# RPi-Camera-RingLicht_v10.net
KiCad netlist of a schematic drawn in EAGLE
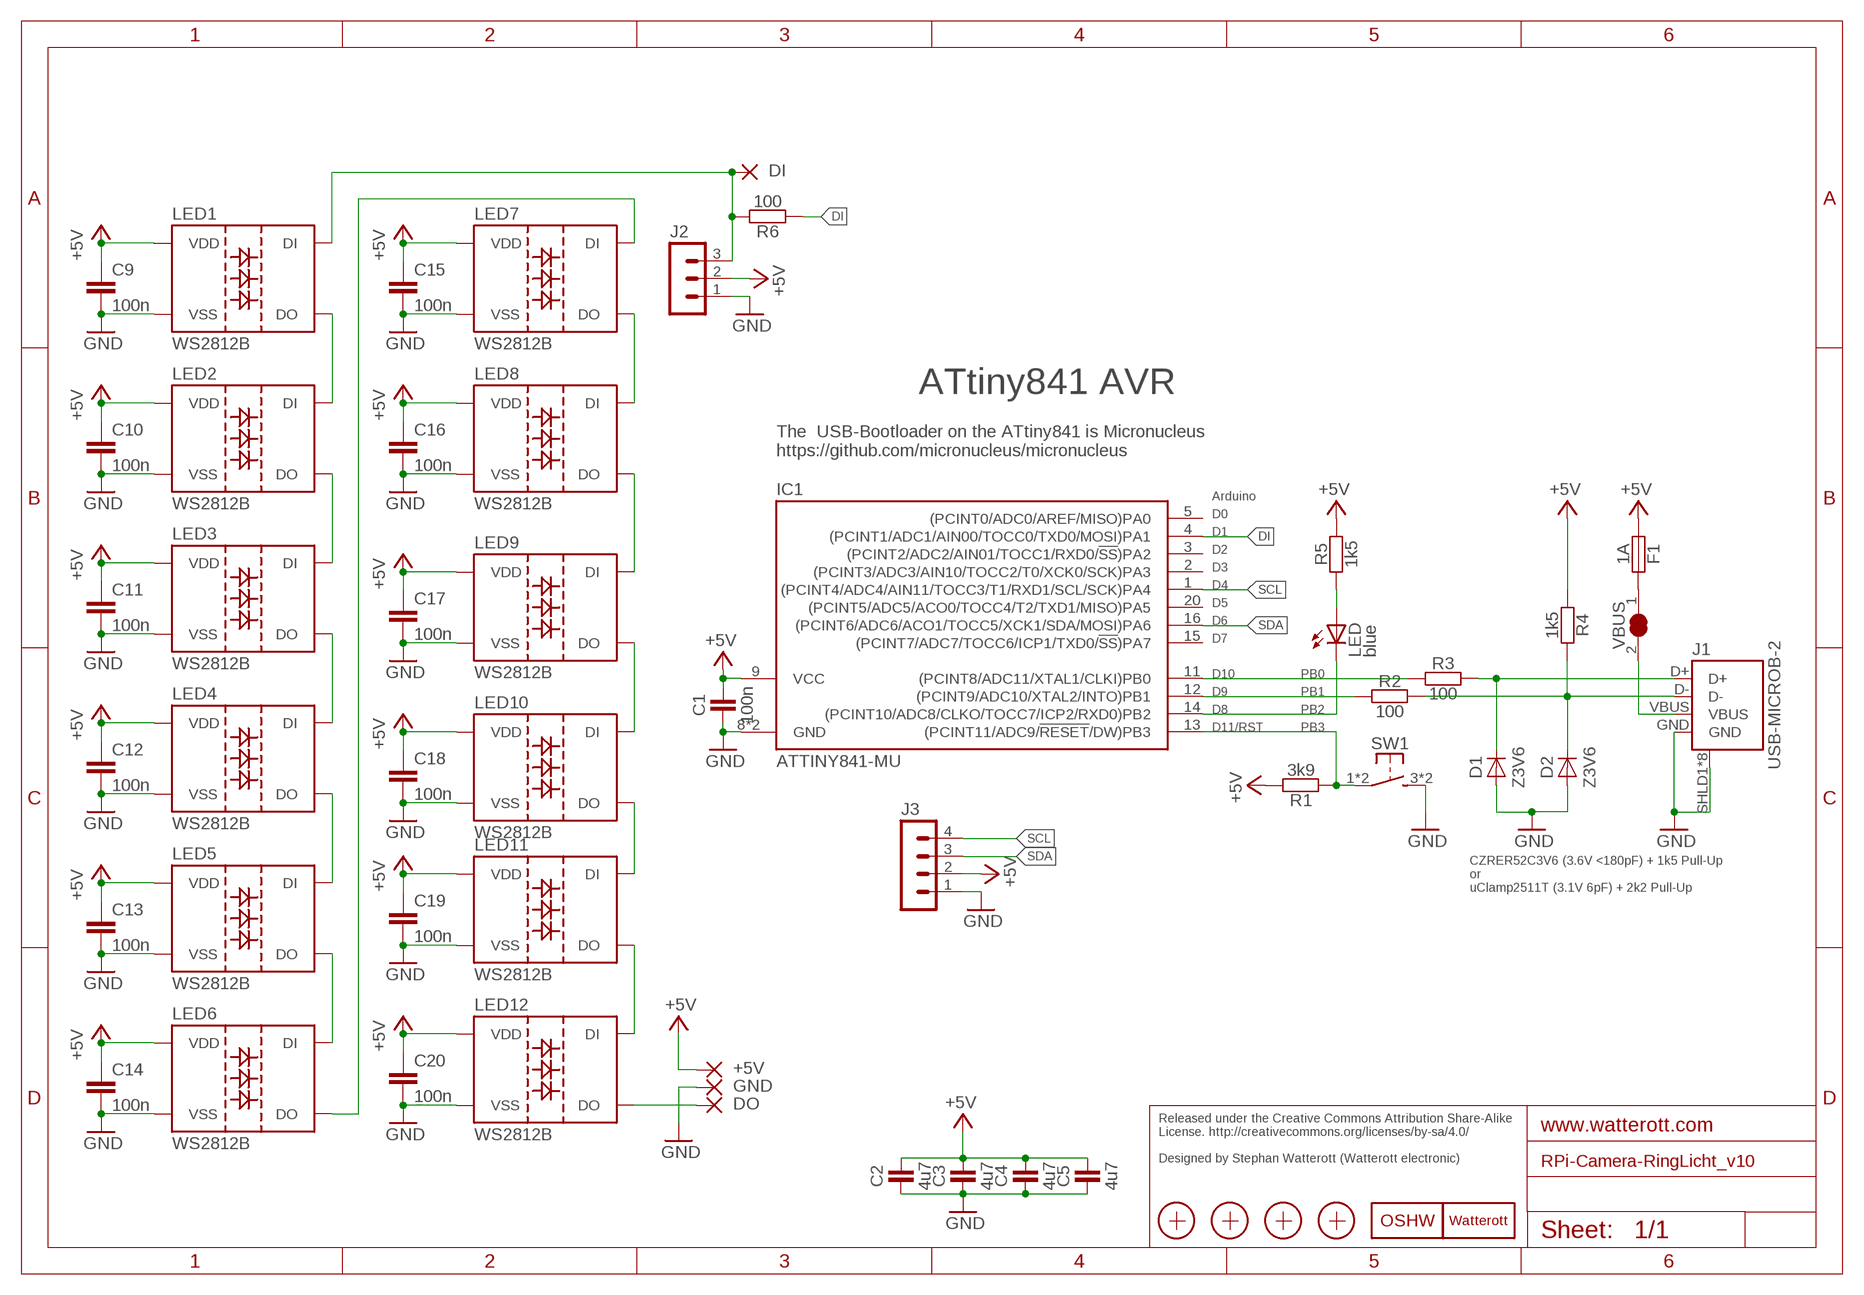
[diagram p0: schematic, sheet 1]

(export (version "E")
  (design (tool "Eeschema 10.0.6"))
  (components
    (comp (ref "+5V")
      (value "SMD2")
      (footprint "eagle-import:SMD1,27-2,54")
      (libsource (lib "eagle-import") (part "SMD2"))
    )
    (comp (ref "C1")
      (value "100n")
      (footprint "eagle-import:C0402")
      (libsource (lib "eagle-import") (part "CAPACITOR-0402"))
    )
    (comp (ref "C2")
      (value "4u7")
      (footprint "eagle-import:C0402")
      (libsource (lib "eagle-import") (part "CAPACITOR-0402"))
    )
    (comp (ref "C3")
      (value "4u7")
      (footprint "eagle-import:C0402")
      (libsource (lib "eagle-import") (part "CAPACITOR-0402"))
    )
    (comp (ref "C4")
      (value "4u7")
      (footprint "eagle-import:C0402")
      (libsource (lib "eagle-import") (part "CAPACITOR-0402"))
    )
    (comp (ref "C5")
      (value "4u7")
      (footprint "eagle-import:C0402")
      (libsource (lib "eagle-import") (part "CAPACITOR-0402"))
    )
    (comp (ref "C9")
      (value "100n")
      (footprint "eagle-import:C0402K")
      (libsource (lib "eagle-import") (part "C-EUC0402K"))
    )
    (comp (ref "C10")
      (value "100n")
      (footprint "eagle-import:C0402K")
      (libsource (lib "eagle-import") (part "C-EUC0402K"))
    )
    (comp (ref "C11")
      (value "100n")
      (footprint "eagle-import:C0402K")
      (libsource (lib "eagle-import") (part "C-EUC0402K"))
    )
    (comp (ref "C12")
      (value "100n")
      (footprint "eagle-import:C0402K")
      (libsource (lib "eagle-import") (part "C-EUC0402K"))
    )
    (comp (ref "C13")
      (value "100n")
      (footprint "eagle-import:C0402K")
      (libsource (lib "eagle-import") (part "C-EUC0402K"))
    )
    (comp (ref "C14")
      (value "100n")
      (footprint "eagle-import:C0402K")
      (libsource (lib "eagle-import") (part "C-EUC0402K"))
    )
    (comp (ref "C15")
      (value "100n")
      (footprint "eagle-import:C0402K")
      (libsource (lib "eagle-import") (part "C-EUC0402K"))
    )
    (comp (ref "C16")
      (value "100n")
      (footprint "eagle-import:C0402K")
      (libsource (lib "eagle-import") (part "C-EUC0402K"))
    )
    (comp (ref "C17")
      (value "100n")
      (footprint "eagle-import:C0402K")
      (libsource (lib "eagle-import") (part "C-EUC0402K"))
    )
    (comp (ref "C18")
      (value "100n")
      (footprint "eagle-import:C0402K")
      (libsource (lib "eagle-import") (part "C-EUC0402K"))
    )
    (comp (ref "C19")
      (value "100n")
      (footprint "eagle-import:C0402K")
      (libsource (lib "eagle-import") (part "C-EUC0402K"))
    )
    (comp (ref "C20")
      (value "100n")
      (footprint "eagle-import:C0402K")
      (libsource (lib "eagle-import") (part "C-EUC0402K"))
    )
    (comp (ref "D1")
      (value "Z3V6")
      (footprint "eagle-import:SOD882")
      (libsource (lib "eagle-import") (part "DIODE-SOD882"))
    )
    (comp (ref "D2")
      (value "Z3V6")
      (footprint "eagle-import:SOD882")
      (libsource (lib "eagle-import") (part "DIODE-SOD882"))
    )
    (comp (ref "DI")
      (value "SMD2")
      (footprint "eagle-import:SMD1,27-2,54")
      (libsource (lib "eagle-import") (part "SMD2"))
    )
    (comp (ref "DO")
      (value "SMD2")
      (footprint "eagle-import:SMD1,27-2,54")
      (libsource (lib "eagle-import") (part "SMD2"))
    )
    (comp (ref "F1")
      (value "1A")
      (footprint "eagle-import:C0805")
      (libsource (lib "eagle-import") (part "FUSE-0805"))
    )
    (comp (ref "GND")
      (value "SMD2")
      (footprint "eagle-import:SMD1,27-2,54")
      (libsource (lib "eagle-import") (part "SMD2"))
    )
    (comp (ref "IC1")
      (value "ATTINY841-MU")
      (footprint "eagle-import:QFN20-PAD")
      (libsource (lib "eagle-import") (part "ATTINY841-MU"))
    )
    (comp (ref "J1")
      (value "USB-MICROB-2")
      (footprint "eagle-import:USB-MICROB-10118194")
      (libsource (lib "eagle-import") (part "USB-MICROB-2"))
    )
    (comp (ref "J2")
      (value "JST3-S3B-PH-SM4-TB")
      (footprint "eagle-import:JST_S3B-PH-SM4-TB")
      (libsource (lib "eagle-import") (part "JST3-S3B-PH-SM4-TB"))
    )
    (comp (ref "J3")
      (value "JST4-S4B-PH-SM4-TB")
      (footprint "eagle-import:JST_S4B-PH-SM4-TB")
      (libsource (lib "eagle-import") (part "JST4-S4B-PH-SM4-TB"))
    )
    (comp (ref "LED")
      (value "blue")
      (footprint "eagle-import:C0603")
      (libsource (lib "eagle-import") (part "LED-0603"))
    )
    (comp (ref "LED1")
      (value "WS2812B")
      (footprint "eagle-import:WS2812B")
      (libsource (lib "eagle-import") (part "WS2812B"))
    )
    (comp (ref "LED2")
      (value "WS2812B")
      (footprint "eagle-import:WS2812B")
      (libsource (lib "eagle-import") (part "WS2812B"))
    )
    (comp (ref "LED3")
      (value "WS2812B")
      (footprint "eagle-import:WS2812B")
      (libsource (lib "eagle-import") (part "WS2812B"))
    )
    (comp (ref "LED4")
      (value "WS2812B")
      (footprint "eagle-import:WS2812B")
      (libsource (lib "eagle-import") (part "WS2812B"))
    )
    (comp (ref "LED5")
      (value "WS2812B")
      (footprint "eagle-import:WS2812B")
      (libsource (lib "eagle-import") (part "WS2812B"))
    )
    (comp (ref "LED6")
      (value "WS2812B")
      (footprint "eagle-import:WS2812B")
      (libsource (lib "eagle-import") (part "WS2812B"))
    )
    (comp (ref "LED7")
      (value "WS2812B")
      (footprint "eagle-import:WS2812B")
      (libsource (lib "eagle-import") (part "WS2812B"))
    )
    (comp (ref "LED8")
      (value "WS2812B")
      (footprint "eagle-import:WS2812B")
      (libsource (lib "eagle-import") (part "WS2812B"))
    )
    (comp (ref "LED9")
      (value "WS2812B")
      (footprint "eagle-import:WS2812B")
      (libsource (lib "eagle-import") (part "WS2812B"))
    )
    (comp (ref "LED10")
      (value "WS2812B")
      (footprint "eagle-import:WS2812B")
      (libsource (lib "eagle-import") (part "WS2812B"))
    )
    (comp (ref "LED11")
      (value "WS2812B")
      (footprint "eagle-import:WS2812B")
      (libsource (lib "eagle-import") (part "WS2812B"))
    )
    (comp (ref "LED12")
      (value "WS2812B")
      (footprint "eagle-import:WS2812B")
      (libsource (lib "eagle-import") (part "WS2812B"))
    )
    (comp (ref "LOGO1")
      (value "LOGO-S_PLACE_M")
      (footprint "eagle-import:SPARK_TPLACE_M")
      (libsource (lib "eagle-import") (part "LOGO-S_PLACE_M"))
    )
    (comp (ref "LOGO2")
      (value "OSHW_LOGOX0070")
      (footprint "eagle-import:OSHW_6X70")
      (libsource (lib "eagle-import") (part "OSHW_LOGOX0070"))
    )
    (comp (ref "R1")
      (value "3k9")
      (footprint "eagle-import:C0402")
      (libsource (lib "eagle-import") (part "RESISTOR-0402"))
    )
    (comp (ref "R2")
      (value "100")
      (footprint "eagle-import:C0402")
      (libsource (lib "eagle-import") (part "RESISTOR-0402"))
    )
    (comp (ref "R3")
      (value "100")
      (footprint "eagle-import:C0402")
      (libsource (lib "eagle-import") (part "RESISTOR-0402"))
    )
    (comp (ref "R4")
      (value "1k5")
      (footprint "eagle-import:C0402")
      (libsource (lib "eagle-import") (part "RESISTOR-0402"))
    )
    (comp (ref "R5")
      (value "1k5")
      (footprint "eagle-import:C0402")
      (libsource (lib "eagle-import") (part "RESISTOR-0402"))
    )
    (comp (ref "R6")
      (value "100")
      (footprint "eagle-import:C0402")
      (libsource (lib "eagle-import") (part "RESISTOR-0402"))
    )
    (comp (ref "SW1")
      (value "SW-TACTILE-PTS840P")
      (footprint "eagle-import:PTS840P")
      (libsource (lib "eagle-import") (part "SW-TACTILE-PTS840P"))
    )
    (comp (ref "VBUS")
      (value "JUMPER2-0603-NC")
      (footprint "eagle-import:JUMPER2-0603_NC")
      (libsource (lib "eagle-import") (part "JUMPER2-0603-NC"))
    )
    (comp (ref "X1")
      (value "PASSER-07")
      (footprint "eagle-import:PASSER_07MM")
      (libsource (lib "eagle-import") (part "PASSER-07"))
    )
    (comp (ref "X2")
      (value "PASSER-07")
      (footprint "eagle-import:PASSER_07MM")
      (libsource (lib "eagle-import") (part "PASSER-07"))
    )
    (comp (ref "X3")
      (value "PASSER-07")
      (footprint "eagle-import:PASSER_07MM")
      (libsource (lib "eagle-import") (part "PASSER-07"))
    )
    (comp (ref "X4")
      (value "PASSER-07")
      (footprint "eagle-import:PASSER_07MM")
      (libsource (lib "eagle-import") (part "PASSER-07"))
    )
  )
  (nets
    (net (code "1") (name "+5V") (class "Default")
      (node (ref "+5V") (pin "1") (pinfunction "P_1") (pintype "passive"))
      (node (ref "C1") (pin "2") (pinfunction "2_2") (pintype "passive"))
      (node (ref "C10") (pin "1") (pinfunction "1_1") (pintype "passive"))
      (node (ref "C11") (pin "1") (pinfunction "1_1") (pintype "passive"))
      (node (ref "C12") (pin "1") (pinfunction "1_1") (pintype "passive"))
      (node (ref "C13") (pin "1") (pinfunction "1_1") (pintype "passive"))
      (node (ref "C14") (pin "1") (pinfunction "1_1") (pintype "passive"))
      (node (ref "C15") (pin "1") (pinfunction "1_1") (pintype "passive"))
      (node (ref "C16") (pin "1") (pinfunction "1_1") (pintype "passive"))
      (node (ref "C17") (pin "1") (pinfunction "1_1") (pintype "passive"))
      (node (ref "C18") (pin "1") (pinfunction "1_1") (pintype "passive"))
      (node (ref "C19") (pin "1") (pinfunction "1_1") (pintype "passive"))
      (node (ref "C2") (pin "2") (pinfunction "2_2") (pintype "passive"))
      (node (ref "C20") (pin "1") (pinfunction "1_1") (pintype "passive"))
      (node (ref "C3") (pin "2") (pinfunction "2_2") (pintype "passive"))
      (node (ref "C4") (pin "2") (pinfunction "2_2") (pintype "passive"))
      (node (ref "C5") (pin "2") (pinfunction "2_2") (pintype "passive"))
      (node (ref "C9") (pin "1") (pinfunction "1_1") (pintype "passive"))
      (node (ref "F1") (pin "1") (pinfunction "1_1") (pintype "passive"))
      (node (ref "IC1") (pin "9") (pinfunction "VCC_9") (pintype "power_in"))
      (node (ref "J2") (pin "2") (pinfunction "2_2") (pintype "passive"))
      (node (ref "J3") (pin "2") (pinfunction "2_2") (pintype "passive"))
      (node (ref "LED1") (pin "1") (pinfunction "VDD_1") (pintype "bidirectional"))
      (node (ref "LED10") (pin "1") (pinfunction "VDD_1") (pintype "bidirectional"))
      (node (ref "LED11") (pin "1") (pinfunction "VDD_1") (pintype "bidirectional"))
      (node (ref "LED12") (pin "1") (pinfunction "VDD_1") (pintype "bidirectional"))
      (node (ref "LED2") (pin "1") (pinfunction "VDD_1") (pintype "bidirectional"))
      (node (ref "LED3") (pin "1") (pinfunction "VDD_1") (pintype "bidirectional"))
      (node (ref "LED4") (pin "1") (pinfunction "VDD_1") (pintype "bidirectional"))
      (node (ref "LED5") (pin "1") (pinfunction "VDD_1") (pintype "bidirectional"))
      (node (ref "LED6") (pin "1") (pinfunction "VDD_1") (pintype "bidirectional"))
      (node (ref "LED7") (pin "1") (pinfunction "VDD_1") (pintype "bidirectional"))
      (node (ref "LED8") (pin "1") (pinfunction "VDD_1") (pintype "bidirectional"))
      (node (ref "LED9") (pin "1") (pinfunction "VDD_1") (pintype "bidirectional"))
      (node (ref "R1") (pin "2") (pinfunction "2_2") (pintype "passive"))
      (node (ref "R4") (pin "1") (pinfunction "1_1") (pintype "passive"))
      (node (ref "R5") (pin "2") (pinfunction "2_2") (pintype "passive"))
    )
    (net (code "2") (name "/PB0") (class "Default")
      (node (ref "IC1") (pin "11") (pinfunction "(PCINT8/ADC11/XTAL1/CLKI)PB0_11") (pintype "bidirectional"))
      (node (ref "R3") (pin "1") (pinfunction "1_1") (pintype "passive"))
    )
    (net (code "3") (name "/PB1") (class "Default")
      (node (ref "IC1") (pin "12") (pinfunction "(PCINT9/ADC10/XTAL2/INTO)PB1_12") (pintype "bidirectional"))
      (node (ref "R2") (pin "1") (pinfunction "1_1") (pintype "passive"))
    )
    (net (code "4") (name "/PB2") (class "Default")
      (node (ref "IC1") (pin "14") (pinfunction "(PCINT10/ADC8/CLKO/TOCC7/ICP2/RXD0)PB2_14") (pintype "bidirectional"))
      (node (ref "LED") (pin "C") (pinfunction "C_C") (pintype "passive"))
    )
    (net (code "5") (name "/PB3") (class "Default")
      (node (ref "IC1") (pin "13") (pinfunction "(PCINT11/ADC9/~{RESET}/DW)PB3_13") (pintype "bidirectional"))
      (node (ref "R1") (pin "1") (pinfunction "1_1") (pintype "passive"))
      (node (ref "SW1") (pin "1") (pinfunction "P1_1") (pintype "passive"))
      (node (ref "SW1") (pin "2") (pinfunction "P1_2") (pintype "passive"))
    )
    (net (code "6") (name "DI") (class "Default")
      (node (ref "IC1") (pin "4") (pinfunction "(PCINT1/ADC1/AIN00/TOCC0/TXD0/MOSI)PA1_4") (pintype "bidirectional"))
      (node (ref "R6") (pin "1") (pinfunction "1_1") (pintype "passive"))
    )
    (net (code "7") (name "GND") (class "Default")
      (node (ref "C1") (pin "1") (pinfunction "1_1") (pintype "passive"))
      (node (ref "C10") (pin "2") (pinfunction "2_2") (pintype "passive"))
      (node (ref "C11") (pin "2") (pinfunction "2_2") (pintype "passive"))
      (node (ref "C12") (pin "2") (pinfunction "2_2") (pintype "passive"))
      (node (ref "C13") (pin "2") (pinfunction "2_2") (pintype "passive"))
      (node (ref "C14") (pin "2") (pinfunction "2_2") (pintype "passive"))
      (node (ref "C15") (pin "2") (pinfunction "2_2") (pintype "passive"))
      (node (ref "C16") (pin "2") (pinfunction "2_2") (pintype "passive"))
      (node (ref "C17") (pin "2") (pinfunction "2_2") (pintype "passive"))
      (node (ref "C18") (pin "2") (pinfunction "2_2") (pintype "passive"))
      (node (ref "C19") (pin "2") (pinfunction "2_2") (pintype "passive"))
      (node (ref "C2") (pin "1") (pinfunction "1_1") (pintype "passive"))
      (node (ref "C20") (pin "2") (pinfunction "2_2") (pintype "passive"))
      (node (ref "C3") (pin "1") (pinfunction "1_1") (pintype "passive"))
      (node (ref "C4") (pin "1") (pinfunction "1_1") (pintype "passive"))
      (node (ref "C5") (pin "1") (pinfunction "1_1") (pintype "passive"))
      (node (ref "C9") (pin "2") (pinfunction "2_2") (pintype "passive"))
      (node (ref "D1") (pin "A") (pinfunction "A_A") (pintype "passive"))
      (node (ref "D2") (pin "A") (pinfunction "A_A") (pintype "passive"))
      (node (ref "GND") (pin "1") (pinfunction "P_1") (pintype "passive"))
      (node (ref "IC1") (pin "8") (pinfunction "GND_8") (pintype "power_in"))
      (node (ref "IC1") (pin "TP") (pinfunction "GND_TP") (pintype "power_in"))
      (node (ref "J1") (pin "GND") (pinfunction "GND_GND") (pintype "power_in"))
      (node (ref "J1") (pin "SHLD1") (pinfunction "SHIELD_SHLD1") (pintype "passive"))
      (node (ref "J1") (pin "SHLD2") (pinfunction "SHIELD_SHLD2") (pintype "passive"))
      (node (ref "J1") (pin "SHLD3") (pinfunction "SHIELD_SHLD3") (pintype "passive"))
      (node (ref "J1") (pin "SHLD4") (pinfunction "SHIELD_SHLD4") (pintype "passive"))
      (node (ref "J1") (pin "SHLD5") (pinfunction "SHIELD_SHLD5") (pintype "passive"))
      (node (ref "J1") (pin "SHLD6") (pinfunction "SHIELD_SHLD6") (pintype "passive"))
      (node (ref "J1") (pin "SHLD7") (pinfunction "SHIELD_SHLD7") (pintype "passive"))
      (node (ref "J1") (pin "SHLD8") (pinfunction "SHIELD_SHLD8") (pintype "passive"))
      (node (ref "J2") (pin "1") (pinfunction "1_1") (pintype "passive"))
      (node (ref "J3") (pin "1") (pinfunction "1_1") (pintype "passive"))
      (node (ref "LED1") (pin "3") (pinfunction "VSS_3") (pintype "bidirectional"))
      (node (ref "LED10") (pin "3") (pinfunction "VSS_3") (pintype "bidirectional"))
      (node (ref "LED11") (pin "3") (pinfunction "VSS_3") (pintype "bidirectional"))
      (node (ref "LED12") (pin "3") (pinfunction "VSS_3") (pintype "bidirectional"))
      (node (ref "LED2") (pin "3") (pinfunction "VSS_3") (pintype "bidirectional"))
      (node (ref "LED3") (pin "3") (pinfunction "VSS_3") (pintype "bidirectional"))
      (node (ref "LED4") (pin "3") (pinfunction "VSS_3") (pintype "bidirectional"))
      (node (ref "LED5") (pin "3") (pinfunction "VSS_3") (pintype "bidirectional"))
      (node (ref "LED6") (pin "3") (pinfunction "VSS_3") (pintype "bidirectional"))
      (node (ref "LED7") (pin "3") (pinfunction "VSS_3") (pintype "bidirectional"))
      (node (ref "LED8") (pin "3") (pinfunction "VSS_3") (pintype "bidirectional"))
      (node (ref "LED9") (pin "3") (pinfunction "VSS_3") (pintype "bidirectional"))
      (node (ref "SW1") (pin "3") (pinfunction "S1_3") (pintype "passive"))
      (node (ref "SW1") (pin "4") (pinfunction "S1_4") (pintype "passive"))
    )
    (net (code "8") (name "Net-(D1-PadC)") (class "Default")
      (node (ref "D1") (pin "C") (pinfunction "C_C") (pintype "passive"))
      (node (ref "J1") (pin "D+") (pinfunction "D+_D+") (pintype "bidirectional"))
      (node (ref "R3") (pin "2") (pinfunction "2_2") (pintype "passive"))
    )
    (net (code "9") (name "Net-(D2-PadC)") (class "Default")
      (node (ref "D2") (pin "C") (pinfunction "C_C") (pintype "passive"))
      (node (ref "J1") (pin "D-") (pinfunction "D-_D-") (pintype "bidirectional"))
      (node (ref "R2") (pin "2") (pinfunction "2_2") (pintype "passive"))
      (node (ref "R4") (pin "2") (pinfunction "2_2") (pintype "passive"))
    )
    (net (code "10") (name "Net-(DI-P)") (class "Default")
      (node (ref "DI") (pin "1") (pinfunction "P_1") (pintype "passive"))
      (node (ref "J2") (pin "3") (pinfunction "3_3") (pintype "passive"))
      (node (ref "LED1") (pin "4") (pinfunction "DI_4") (pintype "bidirectional"))
      (node (ref "R6") (pin "2") (pinfunction "2_2") (pintype "passive"))
    )
    (net (code "11") (name "Net-(DO-P)") (class "Default")
      (node (ref "DO") (pin "1") (pinfunction "P_1") (pintype "passive"))
      (node (ref "LED12") (pin "2") (pinfunction "DO_2") (pintype "bidirectional"))
    )
    (net (code "12") (name "Net-(F1-Pad2)") (class "Default")
      (node (ref "F1") (pin "2") (pinfunction "2_2") (pintype "passive"))
      (node (ref "VBUS") (pin "1") (pinfunction "1_1") (pintype "passive"))
    )
    (net (code "13") (name "Net-(J1-PadVBUS)") (class "Default")
      (node (ref "J1") (pin "VBUS") (pinfunction "VBUS_VBUS") (pintype "power_in"))
      (node (ref "VBUS") (pin "2") (pinfunction "2_2") (pintype "passive"))
    )
    (net (code "14") (name "Net-(LED-PadA)") (class "Default")
      (node (ref "LED") (pin "A") (pinfunction "A_A") (pintype "passive"))
      (node (ref "R5") (pin "1") (pinfunction "1_1") (pintype "passive"))
    )
    (net (code "15") (name "Net-(LED1-DO)") (class "Default")
      (node (ref "LED1") (pin "2") (pinfunction "DO_2") (pintype "bidirectional"))
      (node (ref "LED2") (pin "4") (pinfunction "DI_4") (pintype "bidirectional"))
    )
    (net (code "16") (name "Net-(LED2-DO)") (class "Default")
      (node (ref "LED2") (pin "2") (pinfunction "DO_2") (pintype "bidirectional"))
      (node (ref "LED3") (pin "4") (pinfunction "DI_4") (pintype "bidirectional"))
    )
    (net (code "17") (name "Net-(LED3-DO)") (class "Default")
      (node (ref "LED3") (pin "2") (pinfunction "DO_2") (pintype "bidirectional"))
      (node (ref "LED4") (pin "4") (pinfunction "DI_4") (pintype "bidirectional"))
    )
    (net (code "18") (name "Net-(LED4-DO)") (class "Default")
      (node (ref "LED4") (pin "2") (pinfunction "DO_2") (pintype "bidirectional"))
      (node (ref "LED5") (pin "4") (pinfunction "DI_4") (pintype "bidirectional"))
    )
    (net (code "19") (name "Net-(LED5-DO)") (class "Default")
      (node (ref "LED5") (pin "2") (pinfunction "DO_2") (pintype "bidirectional"))
      (node (ref "LED6") (pin "4") (pinfunction "DI_4") (pintype "bidirectional"))
    )
    (net (code "20") (name "Net-(LED6-DO)") (class "Default")
      (node (ref "LED6") (pin "2") (pinfunction "DO_2") (pintype "bidirectional"))
      (node (ref "LED7") (pin "4") (pinfunction "DI_4") (pintype "bidirectional"))
    )
    (net (code "21") (name "Net-(LED7-DO)") (class "Default")
      (node (ref "LED7") (pin "2") (pinfunction "DO_2") (pintype "bidirectional"))
      (node (ref "LED8") (pin "4") (pinfunction "DI_4") (pintype "bidirectional"))
    )
    (net (code "22") (name "Net-(LED8-DO)") (class "Default")
      (node (ref "LED8") (pin "2") (pinfunction "DO_2") (pintype "bidirectional"))
      (node (ref "LED9") (pin "4") (pinfunction "DI_4") (pintype "bidirectional"))
    )
    (net (code "23") (name "Net-(LED10-DI)") (class "Default")
      (node (ref "LED10") (pin "4") (pinfunction "DI_4") (pintype "bidirectional"))
      (node (ref "LED9") (pin "2") (pinfunction "DO_2") (pintype "bidirectional"))
    )
    (net (code "24") (name "Net-(LED10-DO)") (class "Default")
      (node (ref "LED10") (pin "2") (pinfunction "DO_2") (pintype "bidirectional"))
      (node (ref "LED11") (pin "4") (pinfunction "DI_4") (pintype "bidirectional"))
    )
    (net (code "25") (name "Net-(LED11-DO)") (class "Default")
      (node (ref "LED11") (pin "2") (pinfunction "DO_2") (pintype "bidirectional"))
      (node (ref "LED12") (pin "4") (pinfunction "DI_4") (pintype "bidirectional"))
    )
    (net (code "26") (name "SCL") (class "Default")
      (node (ref "IC1") (pin "1") (pinfunction "(PCINT4/ADC4/AIN11/TOCC3/T1/RXD1/SCL/SCK)PA4_1") (pintype "bidirectional"))
      (node (ref "J3") (pin "4") (pinfunction "4_4") (pintype "passive"))
    )
    (net (code "27") (name "SDA") (class "Default")
      (node (ref "IC1") (pin "16") (pinfunction "(PCINT6/ADC6/ACO1/TOCC5/XCK1/SDA/MOSI)PA6_16") (pintype "bidirectional"))
      (node (ref "J3") (pin "3") (pinfunction "3_3") (pintype "passive"))
    )
    (net (code "28") (name "unconnected-(IC1-(PCINT0{slash}ADC0{slash}AREF{slash}MISO)PA0-Pad5)") (class "Default")
      (node (ref "IC1") (pin "5") (pinfunction "(PCINT0/ADC0/AREF/MISO)PA0_5") (pintype "bidirectional"))
    )
    (net (code "29") (name "unconnected-(IC1-(PCINT2{slash}ADC2{slash}AIN01{slash}TOCC1{slash}RXD0{slash}~{SS})PA2-Pad3)") (class "Default")
      (node (ref "IC1") (pin "3") (pinfunction "(PCINT2/ADC2/AIN01/TOCC1/RXD0/~{SS})PA2_3") (pintype "bidirectional"))
    )
    (net (code "30") (name "unconnected-(IC1-(PCINT3{slash}ADC3{slash}AIN10{slash}TOCC2{slash}T0{slash}XCK0{slash}SCK)PA3-Pad2)") (class "Default")
      (node (ref "IC1") (pin "2") (pinfunction "(PCINT3/ADC3/AIN10/TOCC2/T0/XCK0/SCK)PA3_2") (pintype "bidirectional"))
    )
    (net (code "31") (name "unconnected-(IC1-(PCINT5{slash}ADC5{slash}ACO0{slash}TOCC4{slash}T2{slash}TXD1{slash}MISO)PA5-Pad20)") (class "Default")
      (node (ref "IC1") (pin "20") (pinfunction "(PCINT5/ADC5/ACO0/TOCC4/T2/TXD1/MISO)PA5_20") (pintype "bidirectional"))
    )
    (net (code "32") (name "unconnected-(IC1-(PCINT7{slash}ADC7{slash}TOCC6{slash}ICP1{slash}TXD0{slash}~{SS})PA7-Pad15)") (class "Default")
      (node (ref "IC1") (pin "15") (pinfunction "(PCINT7/ADC7/TOCC6/ICP1/TXD0/~{SS})PA7_15") (pintype "bidirectional"))
    )
  )
)
